# v1.net
KiCad netlist of a schematic drawn in EAGLE
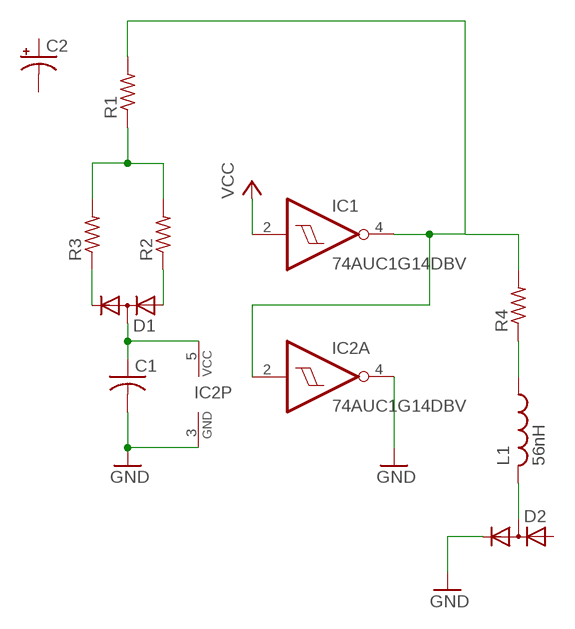
[diagram p0: schematic, sheet 1]

(export (version "E")
  (design (tool "Eeschema 10.0.6"))
  (components
    (comp (ref "C1")
      (value "C-USC0402")
      (footprint "eagle-import:C0402")
      (libsource (lib "eagle-import") (part "C-USC0402"))
    )
    (comp (ref "C2")
      (value "CPOL-USB")
      (footprint "eagle-import:PANASONIC_B")
      (libsource (lib "eagle-import") (part "CPOL-USB"))
    )
    (comp (ref "D1")
      (value "DIODE_2CACA-SOT23")
      (footprint "eagle-import:SOT23")
      (libsource (lib "eagle-import") (part "DIODE_2CACA-SOT23"))
    )
    (comp (ref "D2")
      (value "DIODE_2CACA-SOT23")
      (footprint "eagle-import:SOT23")
      (libsource (lib "eagle-import") (part "DIODE_2CACA-SOT23"))
    )
    (comp (ref "IC1")
      (value "74AUC1G14DBV")
      (footprint "eagle-import:SOT23-5")
      (libsource (lib "eagle-import") (part "741G14DBVAUC"))
    )
    (comp (ref "IC2")
      (value "74AUC1G14DBV")
      (footprint "eagle-import:SOT23-5")
      (libsource (lib "eagle-import") (part "74xx-little-us-edited_741G14DBVAUC"))
    )
    (comp (ref "L1")
      (value "56nH")
      (footprint "eagle-import:L2012C")
      (libsource (lib "eagle-import") (part "L-USL2012C"))
    )
    (comp (ref "R1")
      (value "R-US_R0805")
      (footprint "eagle-import:R0805")
      (libsource (lib "eagle-import") (part "R-US_R0805"))
    )
    (comp (ref "R2")
      (value "R-US_R0805")
      (footprint "eagle-import:R0805")
      (libsource (lib "eagle-import") (part "R-US_R0805"))
    )
    (comp (ref "R3")
      (value "R-US_R0805")
      (footprint "eagle-import:R0805")
      (libsource (lib "eagle-import") (part "R-US_R0805"))
    )
    (comp (ref "R4")
      (value "R-US_R0805")
      (footprint "eagle-import:R0805")
      (libsource (lib "eagle-import") (part "R-US_R0805"))
    )
  )
  (nets
    (net (code "1") (name "GND") (class "Default")
      (node (ref "C1") (pin "2") (pinfunction "2_2") (pintype "passive"))
      (node (ref "D2") (pin "2") (pinfunction "C_2") (pintype "passive"))
      (node (ref "IC2") (pin "3") (pinfunction "3_3") (pintype "power_in"))
      (node (ref "IC2") (pin "4") (pinfunction "O_4") (pintype "output"))
    )
    (net (code "2") (name "Net-(D1-A)") (class "Default")
      (node (ref "D1") (pin "1") (pinfunction "A_1") (pintype "passive"))
      (node (ref "R2") (pin "1") (pinfunction "1_1") (pintype "passive"))
    )
    (net (code "3") (name "Net-(D1-AC)") (class "Default")
      (node (ref "C1") (pin "1") (pinfunction "1_1") (pintype "passive"))
      (node (ref "D1") (pin "3") (pinfunction "AC_3") (pintype "passive"))
      (node (ref "IC2") (pin "5") (pinfunction "5_5") (pintype "power_in"))
    )
    (net (code "4") (name "Net-(D1-C)") (class "Default")
      (node (ref "D1") (pin "2") (pinfunction "C_2") (pintype "passive"))
      (node (ref "R3") (pin "1") (pinfunction "1_1") (pintype "passive"))
    )
    (net (code "5") (name "Net-(D2-AC)") (class "Default")
      (node (ref "D2") (pin "3") (pinfunction "AC_3") (pintype "passive"))
      (node (ref "L1") (pin "2") (pinfunction "2_2") (pintype "passive"))
    )
    (net (code "6") (name "Net-(IC1A-O)") (class "Default")
      (node (ref "IC1") (pin "4") (pinfunction "O_4") (pintype "output"))
      (node (ref "IC2") (pin "2") (pinfunction "I_2") (pintype "input"))
      (node (ref "R1") (pin "2") (pinfunction "2_2") (pintype "passive"))
      (node (ref "R4") (pin "2") (pinfunction "2_2") (pintype "passive"))
    )
    (net (code "7") (name "Net-(L1-Pad1)") (class "Default")
      (node (ref "L1") (pin "1") (pinfunction "1_1") (pintype "passive"))
      (node (ref "R4") (pin "1") (pinfunction "1_1") (pintype "passive"))
    )
    (net (code "8") (name "Net-(R1-Pad1)") (class "Default")
      (node (ref "R1") (pin "1") (pinfunction "1_1") (pintype "passive"))
      (node (ref "R2") (pin "2") (pinfunction "2_2") (pintype "passive"))
      (node (ref "R3") (pin "2") (pinfunction "2_2") (pintype "passive"))
    )
    (net (code "9") (name "VCC") (class "Default")
      (node (ref "IC1") (pin "2") (pinfunction "I_2") (pintype "input"))
    )
    (net (code "10") (name "unconnected-(C2-Pad+)") (class "Default")
      (node (ref "C2") (pin "+") (pinfunction "+_+") (pintype "passive"))
    )
    (net (code "11") (name "unconnected-(C2-Pad-)") (class "Default")
      (node (ref "C2") (pin "-") (pinfunction "-_-") (pintype "passive"))
    )
    (net (code "12") (name "unconnected-(D2-A-Pad1)") (class "Default")
      (node (ref "D2") (pin "1") (pinfunction "A_1") (pintype "passive"))
    )
  )
)
